# Adafruit_MCP4725_QT.net
KiCad netlist of a schematic drawn in EAGLE
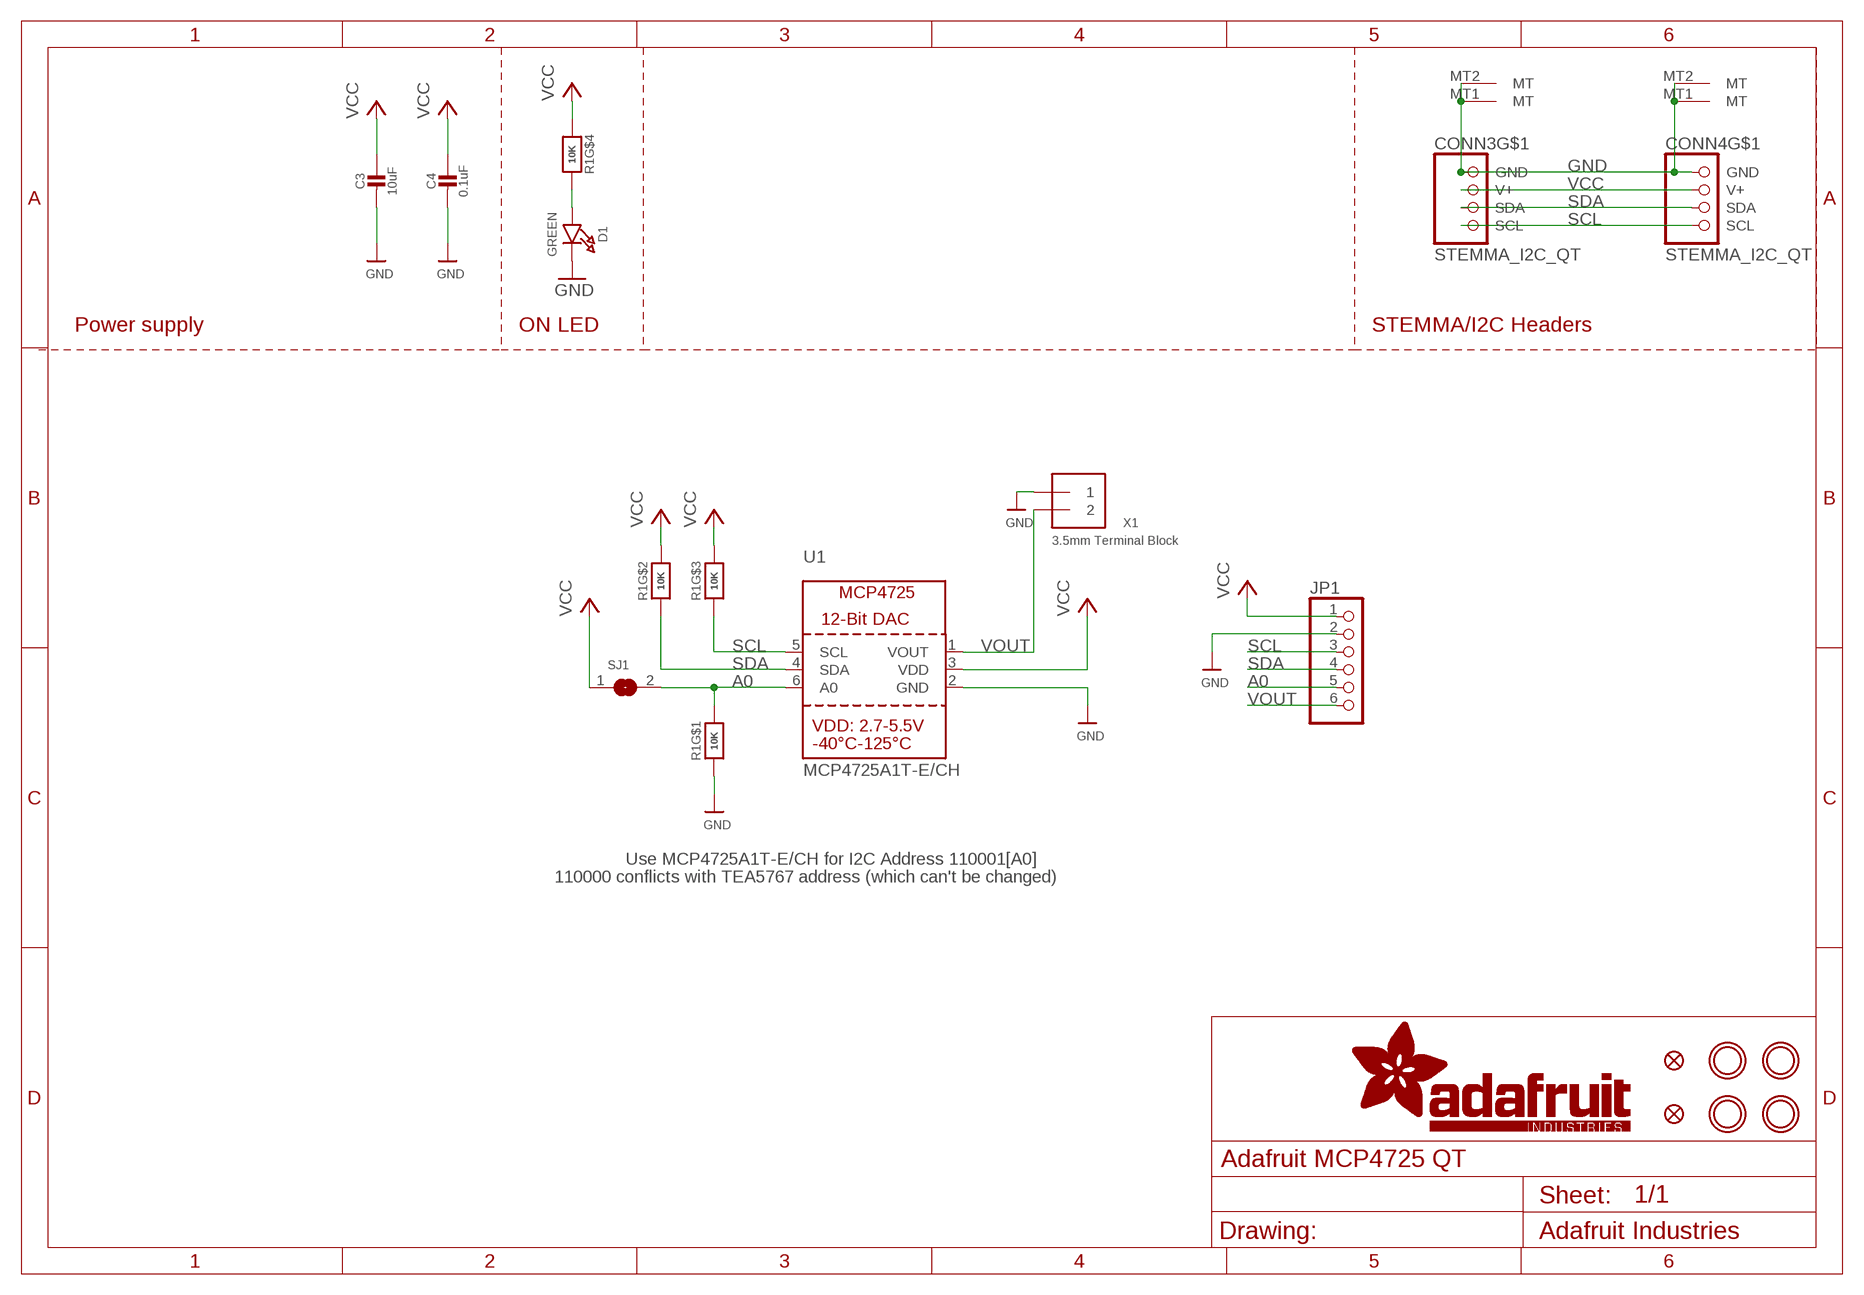
[diagram p0: schematic, sheet 1]

(export (version "E")
  (design (tool "Eeschema 10.0.6"))
  (components
    (comp (ref "C3")
      (value "10uF")
      (footprint "eagle-import:0805-NO")
      (libsource (lib "eagle-import") (part "CAP_CERAMIC0805-NOOUTLINE"))
    )
    (comp (ref "C4")
      (value "0.1uF")
      (footprint "eagle-import:0603-NO")
      (libsource (lib "eagle-import") (part "CAP_CERAMIC0603_NO"))
    )
    (comp (ref "CONN3")
      (value "STEMMA_I2C_QT")
      (footprint "eagle-import:JST_SH4")
      (libsource (lib "eagle-import") (part "STEMMA_I2C_QT"))
    )
    (comp (ref "CONN4")
      (value "STEMMA_I2C_QT")
      (footprint "eagle-import:JST_SH4")
      (libsource (lib "eagle-import") (part "STEMMA_I2C_QT"))
    )
    (comp (ref "D1")
      (value "GREEN")
      (footprint "eagle-import:CHIPLED_0603_NOOUTLINE")
      (libsource (lib "eagle-import") (part "LED0603_NOOUTLINE"))
    )
    (comp (ref "FID3")
      (value "FIDUCIAL_1MM")
      (footprint "eagle-import:FIDUCIAL_1MM")
      (libsource (lib "eagle-import") (part "FIDUCIAL_1MM"))
    )
    (comp (ref "FID4")
      (value "FIDUCIAL_1MM")
      (footprint "eagle-import:FIDUCIAL_1MM")
      (libsource (lib "eagle-import") (part "FIDUCIAL_1MM"))
    )
    (comp (ref "JP1")
      (value "HEADER-1X670MIL")
      (footprint "eagle-import:1X06_ROUND_70")
      (libsource (lib "eagle-import") (part "HEADER-1X670MIL"))
    )
    (comp (ref "R1")
      (value "10K")
      (footprint "eagle-import:RESPACK_4X0603")
      (libsource (lib "eagle-import") (part "RESISTOR_4PACK"))
    )
    (comp (ref "SJ1")
      (value "SOLDERJUMPER")
      (footprint "eagle-import:SOLDERJUMPER_ARROW_NOPASTE")
      (libsource (lib "eagle-import") (part "SOLDERJUMPER"))
    )
    (comp (ref "U$20")
      (value "MOUNTINGHOLE2.5")
      (footprint "eagle-import:MOUNTINGHOLE_2.5_PLATED")
      (libsource (lib "eagle-import") (part "MOUNTINGHOLE2.5"))
    )
    (comp (ref "U$21")
      (value "MOUNTINGHOLE2.5")
      (footprint "eagle-import:MOUNTINGHOLE_2.5_PLATED")
      (libsource (lib "eagle-import") (part "MOUNTINGHOLE2.5"))
    )
    (comp (ref "U$25")
      (value "MOUNTINGHOLE2.5")
      (footprint "eagle-import:MOUNTINGHOLE_2.5_PLATED")
      (libsource (lib "eagle-import") (part "MOUNTINGHOLE2.5"))
    )
    (comp (ref "U$27")
      (value "MOUNTINGHOLE2.5")
      (footprint "eagle-import:MOUNTINGHOLE_2.5_PLATED")
      (libsource (lib "eagle-import") (part "MOUNTINGHOLE2.5"))
    )
    (comp (ref "U1")
      (value "MCP4725A1T-E/CH")
      (footprint "eagle-import:SOT23-6")
      (libsource (lib "eagle-import") (part "DAC_MCP4725"))
    )
    (comp (ref "X1")
      (value "3.5mm Terminal Block")
      (footprint "eagle-import:TERMBLOCK_1X2-3.5MM")
      (libsource (lib "eagle-import") (part "TERMBLOCK_1X2_3.5MM"))
    )
  )
  (nets
    (net (code "1") (name "/A0") (class "Default")
      (node (ref "JP1") (pin "5") (pinfunction "5_5") (pintype "passive"))
      (node (ref "R1") (pin "8") (pinfunction "2_8") (pintype "passive"))
      (node (ref "SJ1") (pin "2") (pinfunction "2_2") (pintype "passive"))
      (node (ref "U1") (pin "6") (pinfunction "A0_6") (pintype "input"))
    )
    (net (code "2") (name "/SCL") (class "Default")
      (node (ref "CONN3") (pin "4") (pinfunction "SCL_4") (pintype "passive"))
      (node (ref "CONN4") (pin "4") (pinfunction "SCL_4") (pintype "passive"))
      (node (ref "JP1") (pin "3") (pinfunction "3_3") (pintype "passive"))
      (node (ref "R1") (pin "3") (pinfunction "1_3") (pintype "passive"))
      (node (ref "U1") (pin "5") (pinfunction "SCL_5") (pintype "bidirectional"))
    )
    (net (code "3") (name "/SDA") (class "Default")
      (node (ref "CONN3") (pin "3") (pinfunction "SDA_3") (pintype "passive"))
      (node (ref "CONN4") (pin "3") (pinfunction "SDA_3") (pintype "passive"))
      (node (ref "JP1") (pin "4") (pinfunction "4_4") (pintype "passive"))
      (node (ref "R1") (pin "2") (pinfunction "1_2") (pintype "passive"))
      (node (ref "U1") (pin "4") (pinfunction "SDA_4") (pintype "bidirectional"))
    )
    (net (code "4") (name "/VOUT") (class "Default")
      (node (ref "JP1") (pin "6") (pinfunction "6_6") (pintype "passive"))
      (node (ref "U1") (pin "1") (pinfunction "VOUT_1") (pintype "output"))
      (node (ref "X1") (pin "2") (pinfunction "2_2") (pintype "passive"))
    )
    (net (code "5") (name "GND") (class "Default")
      (node (ref "C3") (pin "2") (pinfunction "2_2") (pintype "passive"))
      (node (ref "C4") (pin "2") (pinfunction "2_2") (pintype "passive"))
      (node (ref "CONN3") (pin "1") (pinfunction "GND_1") (pintype "passive"))
      (node (ref "CONN3") (pin "MT1") (pinfunction "MT_MT1") (pintype "bidirectional"))
      (node (ref "CONN3") (pin "MT2") (pinfunction "MT_MT2") (pintype "bidirectional"))
      (node (ref "CONN4") (pin "1") (pinfunction "GND_1") (pintype "passive"))
      (node (ref "CONN4") (pin "MT1") (pinfunction "MT_MT1") (pintype "bidirectional"))
      (node (ref "CONN4") (pin "MT2") (pinfunction "MT_MT2") (pintype "bidirectional"))
      (node (ref "D1") (pin "C") (pinfunction "C_C") (pintype "passive"))
      (node (ref "JP1") (pin "2") (pinfunction "2_2") (pintype "passive"))
      (node (ref "R1") (pin "1") (pinfunction "1_1") (pintype "passive"))
      (node (ref "U1") (pin "2") (pinfunction "GND_2") (pintype "power_in"))
      (node (ref "X1") (pin "1") (pinfunction "1_1") (pintype "passive"))
    )
    (net (code "6") (name "Net-(R1D-2)") (class "Default")
      (node (ref "D1") (pin "A") (pinfunction "A_A") (pintype "passive"))
      (node (ref "R1") (pin "5") (pinfunction "2_5") (pintype "passive"))
    )
    (net (code "7") (name "VCC") (class "Default")
      (node (ref "C3") (pin "1") (pinfunction "1_1") (pintype "passive"))
      (node (ref "C4") (pin "1") (pinfunction "1_1") (pintype "passive"))
      (node (ref "CONN3") (pin "2") (pinfunction "V+_2") (pintype "passive"))
      (node (ref "CONN4") (pin "2") (pinfunction "V+_2") (pintype "passive"))
      (node (ref "JP1") (pin "1") (pinfunction "1_1") (pintype "passive"))
      (node (ref "R1") (pin "4") (pinfunction "1_4") (pintype "passive"))
      (node (ref "R1") (pin "6") (pinfunction "2_6") (pintype "passive"))
      (node (ref "R1") (pin "7") (pinfunction "2_7") (pintype "passive"))
      (node (ref "SJ1") (pin "1") (pinfunction "1_1") (pintype "passive"))
      (node (ref "U1") (pin "3") (pinfunction "VDD_3") (pintype "power_in"))
    )
  )
)
